# 3V3_MCU_SUPPLY.net
KiCad netlist of a schematic drawn in Altium Designer
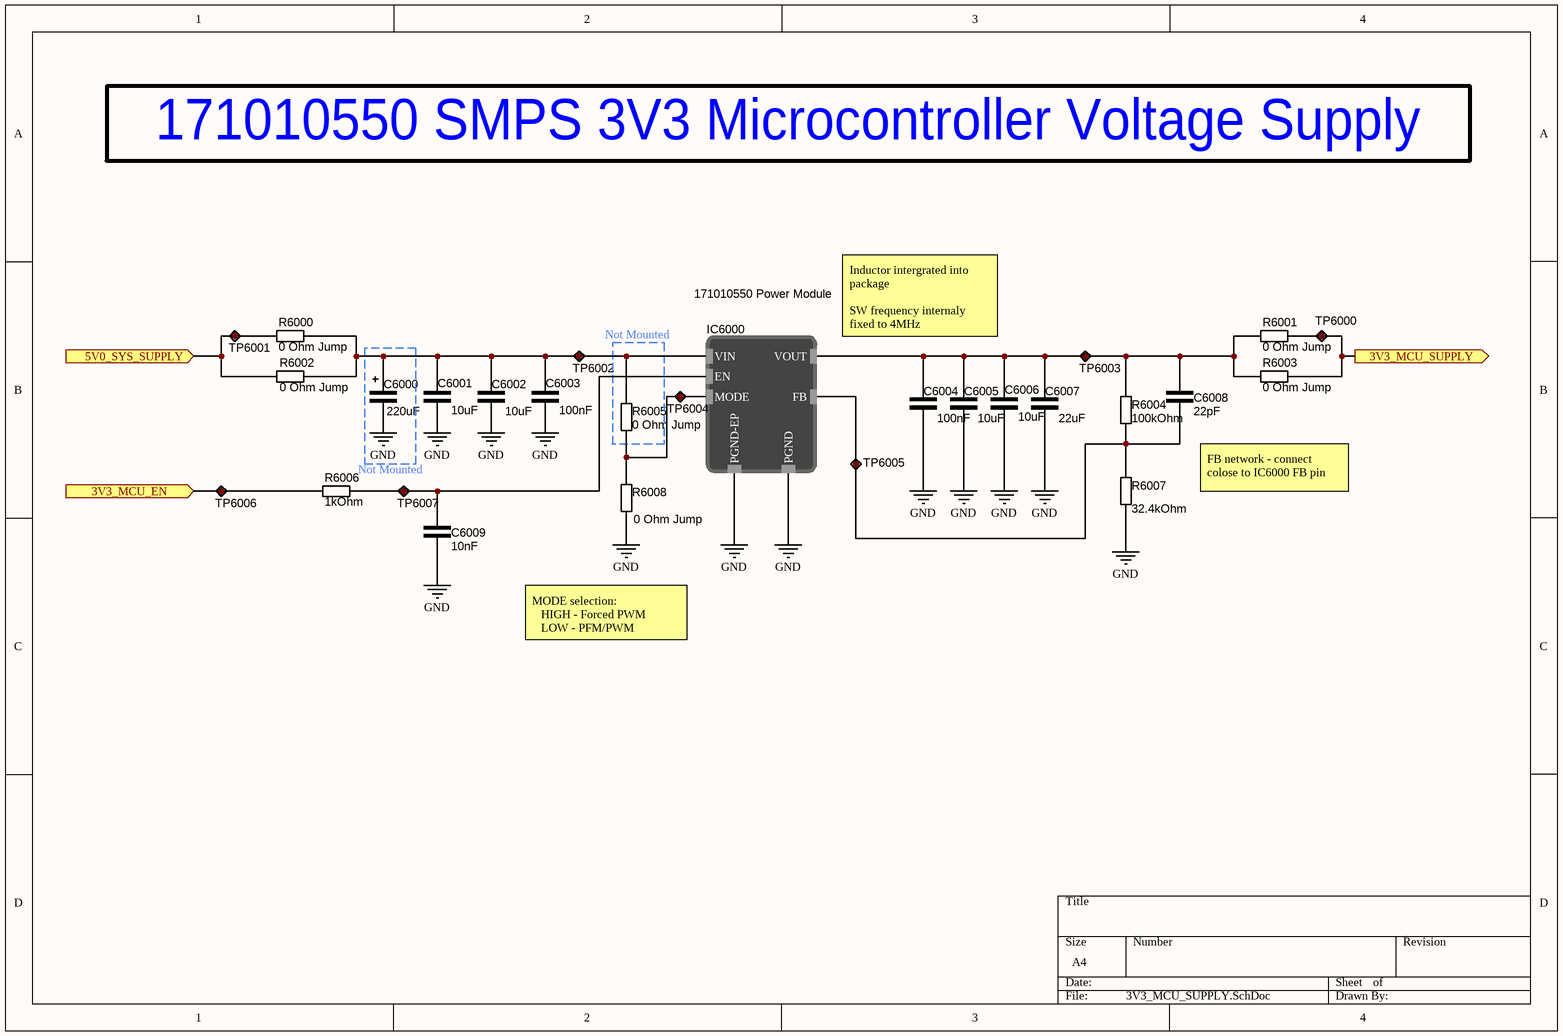
[diagram p0: 3V3_MCU_SUPPLY.SchDoc]

(export (version "E")
  (design (tool "Eeschema 10.0.6"))
  (components
    (comp (ref "C6000")
      (value "220uF")
      (footprint "CAPAE9083X100M")
      (description "220 µF 10 V Aluminum - Polymer Capacitors Radial, Can - SMD 20mOhm 2000 Hrs @ 105°C")
      (fields (field (name "DIGIKEY PART NUMBER") "399-A765KN227M1ALAE020CT-ND"))
      (libsource (lib "CapacitorsIntegrated") (part "C000025"))
    )
    (comp (ref "C6001")
      (value "10uF")
      (footprint "CAP_0805")
      (description "10 µF ±10% 25V Ceramic Capacitor X5R 0805 (2012 Metric)")
      (fields (field (name "DIGIKEY PART NUMBER") "445-5984-1-ND"))
      (libsource (lib "") (part "C000002_1"))
    )
    (comp (ref "C6002")
      (value "10uF")
      (footprint "CAP_0805")
      (description "10 µF ±10% 25V Ceramic Capacitor X5R 0805 (2012 Metric)")
      (fields (field (name "DIGIKEY PART NUMBER") "445-5984-1-ND"))
      (libsource (lib "CapacitorsIntegrated") (part "C000002"))
    )
    (comp (ref "C6003")
      (value "100nF")
      (footprint "CAP_0603")
      (description "0.1 µF ±10% 25V Ceramic Capacitor X7R 0603 (1608 Metric)")
      (fields (field (name "DIGIKEY PART NUMBER") "478-KAM15AR71E104KTCT-ND"))
      (libsource (lib "") (part "C000007_1"))
    )
    (comp (ref "C6004")
      (value "100nF")
      (footprint "CAP_0603")
      (description "0.1 µF ±10% 25V Ceramic Capacitor X7R 0603 (1608 Metric)")
      (fields (field (name "DIGIKEY PART NUMBER") "478-KAM15AR71E104KTCT-ND"))
      (libsource (lib "CapacitorsIntegrated") (part "C000007"))
    )
    (comp (ref "C6005")
      (value "10uF")
      (footprint "CAP_0805")
      (description "10 µF ±10% 25V Ceramic Capacitor X5R 0805 (2012 Metric)")
      (fields (field (name "DIGIKEY PART NUMBER") "445-5984-1-ND"))
      (libsource (lib "CapacitorsIntegrated") (part "C000002"))
    )
    (comp (ref "C6006")
      (value "10uF")
      (footprint "CAP_0805")
      (description "10 µF ±10% 25V Ceramic Capacitor X5R 0805 (2012 Metric)")
      (fields (field (name "DIGIKEY PART NUMBER") "445-5984-1-ND"))
      (libsource (lib "") (part "C000002_1"))
    )
    (comp (ref "C6007")
      (value "22uF")
      (footprint "CAP_0805")
      (description "22 µF ±20% 25V Ceramic Capacitor X5R 0805 (2012 Metric)")
      (fields (field (name "DIGIKEY PART NUMBER") "445-9112-1-ND"))
      (libsource (lib "CapacitorsIntegrated") (part "C000001"))
    )
    (comp (ref "C6008")
      (value "22pF")
      (footprint "CAP_0603")
      (description "22 pF ±10% 25V Ceramic Capacitor X7R 0603 (1608 Metric)")
      (fields (field (name "DIGIKEY PART NUMBER") "399-C0603C220K3RACAUTOCT-ND"))
      (libsource (lib "CapacitorsIntegrated") (part "C000024"))
    )
    (comp (ref "C6009")
      (value "10nF")
      (footprint "CAP_0603")
      (description "10000 pF ±20% 25V Ceramic Capacitor X7R 0603 (1608 Metric)")
      (fields (field (name "DIGIKEY PART NUMBER") "478-KGM15AR71E103MTCT-ND"))
      (libsource (lib "CapacitorsIntegrated") (part "C000005"))
    )
    (comp (ref "IC6000")
      (value "171010550 Power Module")
      (footprint "171010550")
      (description "Non-Isolated PoL Module DC DC Converter 1 Output 0.8 ~ 5.5V 1.2A 2.5V - 5.5V Input")
      (fields
        (field (name "DIGIKEY PART NUMBER") "732-171010550CT-ND")
        (field (name "MOUSER PART NUMBER") "710-171010550")
      )
      (libsource (lib "IntegratedCircuits") (part "171010550"))
    )
    (comp (ref "R6000")
      (value "0 Ohm Jump")
      (footprint "RES_0603")
      (description "0 Ohms Jumper Chip Resistor 0603 (1608 Metric) Automotive AEC-Q200 Thick Film")
      (fields (field (name "DIGIKEY PART NUMBER") "RMCF0603ZT0R00CT-ND"))
      (libsource (lib "") (part "R000007_1"))
    )
    (comp (ref "R6001")
      (value "0 Ohm Jump")
      (footprint "RES_0805")
      (description "0 Ohms Jumper Chip Resistor 0805 (2012 Metric) Automotive AEC-Q200 Thick Film")
      (fields (field (name "DIGIKEY PART NUMBER") "P0.0ACT-ND"))
      (libsource (lib "ResistorsIntegrated") (part "R000011"))
    )
    (comp (ref "R6002")
      (value "0 Ohm Jump")
      (footprint "RES_0603")
      (description "0 Ohms Jumper Chip Resistor 0603 (1608 Metric) Automotive AEC-Q200 Thick Film")
      (fields (field (name "DIGIKEY PART NUMBER") "RMCF0603ZT0R00CT-ND"))
      (libsource (lib "") (part "R000007_2"))
    )
    (comp (ref "R6003")
      (value "0 Ohm Jump")
      (footprint "RES_0805")
      (description "0 Ohms Jumper Chip Resistor 0805 (2012 Metric) Automotive AEC-Q200 Thick Film")
      (fields (field (name "DIGIKEY PART NUMBER") "P0.0ACT-ND"))
      (libsource (lib "ResistorsIntegrated") (part "R000011"))
    )
    (comp (ref "R6004")
      (value "100kOhm")
      (footprint "RES_0603")
      (description "100 kOhms ±1% 0.1W, 1/10W Chip Resistor 0603 (1608 Metric) Automotive AEC-Q200 Thick Film")
      (fields (field (name "DIGIKEY PART NUMBER") "RMCF0603FG100KCT-ND"))
      (libsource (lib "ResistorsIntegrated") (part "R000006"))
    )
    (comp (ref "R6005")
      (value "0 Ohm Jump")
      (footprint "RES_0603")
      (description "0 Ohms Jumper Chip Resistor 0603 (1608 Metric) Automotive AEC-Q200 Thick Film")
      (fields (field (name "DIGIKEY PART NUMBER") "RMCF0603ZT0R00CT-ND"))
      (libsource (lib "ResistorsIntegrated") (part "R000007"))
    )
    (comp (ref "R6006")
      (value "1kOhm")
      (footprint "RES_0603")
      (description "1 kOhms ±1% 0.125W, 1/8W Chip Resistor 0603 (1608 Metric) Anti-Sulfur Thin Film")
      (fields (field (name "DIGIKEY PART NUMBER") "MCT0603-1.00K-CFCT-ND"))
      (libsource (lib "ResistorsIntegrated") (part "R000004"))
    )
    (comp (ref "R6007")
      (value "32.4kOhm")
      (footprint "RES_0603")
      (description "32.4 kOhms ±1% 0.1W, 1/10W Chip Resistor 0603 (1608 Metric) Moisture Resistant Thick Film")
      (fields (field (name "DIGIKEY PART NUMBER") "CR0603-FX-3242ELFCT-ND"))
      (libsource (lib "ResistorsIntegrated") (part "R000014"))
    )
    (comp (ref "R6008")
      (value "0 Ohm Jump")
      (footprint "RES_0603")
      (description "0 Ohms Jumper Chip Resistor 0603 (1608 Metric) Automotive AEC-Q200 Thick Film")
      (fields (field (name "DIGIKEY PART NUMBER") "RMCF0603ZT0R00CT-ND"))
      (libsource (lib "ResistorsIntegrated") (part "R000007"))
    )
    (comp (ref "TP6000")
      (value "Test point")
      (footprint "TestPoint")
      (description "Test point 1mm")
      (libsource (lib "IntegratedCircuits") (part "TP002"))
    )
    (comp (ref "TP6001")
      (value "Test point")
      (footprint "TestPoint")
      (description "Test point 1mm")
      (libsource (lib "IntegratedCircuits") (part "TP002"))
    )
    (comp (ref "TP6002")
      (value "Test point")
      (footprint "TestPoint")
      (description "Test point 1mm")
      (libsource (lib "IntegratedCircuits") (part "TP002"))
    )
    (comp (ref "TP6003")
      (value "Test point")
      (footprint "TestPoint")
      (description "Test point 1mm")
      (libsource (lib "IntegratedCircuits") (part "TP002"))
    )
    (comp (ref "TP6004")
      (value "Test point")
      (footprint "TestPoint")
      (description "Test point 1mm")
      (libsource (lib "IntegratedCircuits") (part "TP002"))
    )
    (comp (ref "TP6005")
      (value "Test point")
      (footprint "TestPoint")
      (description "Test point 1mm")
      (libsource (lib "IntegratedCircuits") (part "TP002"))
    )
    (comp (ref "TP6006")
      (value "Test point")
      (footprint "TestPoint")
      (description "Test point 1mm")
      (libsource (lib "IntegratedCircuits") (part "TP002"))
    )
    (comp (ref "TP6007")
      (value "Test point")
      (footprint "TestPoint")
      (description "Test point 1mm")
      (libsource (lib "IntegratedCircuits") (part "TP002"))
    )
  )
  (nets
    (net (code "1") (name "/3V3_MCU_EN") (class "Default")
      (node (ref "R6006") (pin "1") (pinfunction "1_1") (pintype "passive"))
      (node (ref "TP6006") (pin "1") (pinfunction "1_1") (pintype "passive"))
    )
    (net (code "2") (name "/3V3_MCU_SUPPLY") (class "Default")
      (node (ref "R6001") (pin "2") (pinfunction "2_2") (pintype "passive"))
      (node (ref "R6003") (pin "2") (pinfunction "2_2") (pintype "passive"))
      (node (ref "TP6000") (pin "1") (pinfunction "1_1") (pintype "passive"))
    )
    (net (code "3") (name "/5V0_SYS_SUPPLY") (class "Default")
      (node (ref "R6000") (pin "1") (pinfunction "1_1") (pintype "passive"))
      (node (ref "R6002") (pin "2") (pinfunction "2_2") (pintype "passive"))
      (node (ref "TP6001") (pin "1") (pinfunction "1_1") (pintype "passive"))
    )
    (net (code "4") (name "GND") (class "Default")
      (node (ref "C6004") (pin "1") (pinfunction "1_1") (pintype "passive"))
      (node (ref "C6005") (pin "1") (pinfunction "1_1") (pintype "passive"))
      (node (ref "C6006") (pin "2") (pinfunction "2_2") (pintype "passive"))
      (node (ref "C6007") (pin "2") (pinfunction "2_2") (pintype "passive"))
      (node (ref "C6009") (pin "1") (pinfunction "1_1") (pintype "passive"))
      (node (ref "IC6000") (pin "5") (pinfunction "PGND_5") (pintype "passive"))
      (node (ref "IC6000") (pin "EP") (pinfunction "PGND-EP_EP") (pintype "passive"))
      (node (ref "R6007") (pin "1") (pinfunction "1_1") (pintype "passive"))
      (node (ref "R6008") (pin "1") (pinfunction "1_1") (pintype "passive"))
    )
    (net (code "5") (name "Net-(IC6000-EN)") (class "Default")
      (node (ref "C6009") (pin "2") (pinfunction "2_2") (pintype "passive"))
      (node (ref "IC6000") (pin "3") (pinfunction "EN_3") (pintype "passive"))
      (node (ref "R6006") (pin "2") (pinfunction "2_2") (pintype "passive"))
      (node (ref "TP6007") (pin "1") (pinfunction "1_1") (pintype "passive"))
    )
    (net (code "6") (name "Net-(IC6000-FB)") (class "Default")
      (node (ref "C6008") (pin "1") (pinfunction "1_1") (pintype "passive"))
      (node (ref "IC6000") (pin "1") (pinfunction "FB_1") (pintype "passive"))
      (node (ref "R6004") (pin "1") (pinfunction "1_1") (pintype "passive"))
      (node (ref "R6007") (pin "2") (pinfunction "2_2") (pintype "passive"))
      (node (ref "TP6005") (pin "1") (pinfunction "1_1") (pintype "passive"))
    )
    (net (code "7") (name "Net-(IC6000-MODE)") (class "Default")
      (node (ref "IC6000") (pin "2") (pinfunction "MODE_2") (pintype "passive"))
      (node (ref "R6005") (pin "1") (pinfunction "1_1") (pintype "passive"))
      (node (ref "R6008") (pin "2") (pinfunction "2_2") (pintype "passive"))
      (node (ref "TP6004") (pin "1") (pinfunction "1_1") (pintype "passive"))
    )
    (net (code "8") (name "Net-(IC6000-VIN)") (class "Default")
      (node (ref "C6000") (pin "2") (pinfunction "2_2") (pintype "passive"))
      (node (ref "C6001") (pin "1") (pinfunction "1_1") (pintype "passive"))
      (node (ref "C6002") (pin "2") (pinfunction "2_2") (pintype "passive"))
      (node (ref "C6003") (pin "1") (pinfunction "1_1") (pintype "passive"))
      (node (ref "IC6000") (pin "4") (pinfunction "VIN_4") (pintype "passive"))
      (node (ref "R6000") (pin "2") (pinfunction "2_2") (pintype "passive"))
      (node (ref "R6002") (pin "1") (pinfunction "1_1") (pintype "passive"))
      (node (ref "R6005") (pin "2") (pinfunction "2_2") (pintype "passive"))
      (node (ref "TP6002") (pin "1") (pinfunction "1_1") (pintype "passive"))
    )
    (net (code "9") (name "Net-(IC6000-VOUT)") (class "Default")
      (node (ref "C6004") (pin "2") (pinfunction "2_2") (pintype "passive"))
      (node (ref "C6005") (pin "2") (pinfunction "2_2") (pintype "passive"))
      (node (ref "C6006") (pin "1") (pinfunction "1_1") (pintype "passive"))
      (node (ref "C6007") (pin "1") (pinfunction "1_1") (pintype "passive"))
      (node (ref "C6008") (pin "2") (pinfunction "2_2") (pintype "passive"))
      (node (ref "IC6000") (pin "6") (pinfunction "VOUT_6") (pintype "passive"))
      (node (ref "R6001") (pin "1") (pinfunction "1_1") (pintype "passive"))
      (node (ref "R6003") (pin "1") (pinfunction "1_1") (pintype "passive"))
      (node (ref "R6004") (pin "2") (pinfunction "2_2") (pintype "passive"))
      (node (ref "TP6003") (pin "1") (pinfunction "1_1") (pintype "passive"))
    )
    (net (code "10") (name "unconnected-(C6000-Pad1)") (class "Default")
      (node (ref "C6000") (pin "1") (pinfunction "1_1") (pintype "passive"))
    )
    (net (code "11") (name "unconnected-(C6001-Pad2)") (class "Default")
      (node (ref "C6001") (pin "2") (pinfunction "2_2") (pintype "passive"))
    )
    (net (code "12") (name "unconnected-(C6002-Pad1)") (class "Default")
      (node (ref "C6002") (pin "1") (pinfunction "1_1") (pintype "passive"))
    )
    (net (code "13") (name "unconnected-(C6003-Pad2)") (class "Default")
      (node (ref "C6003") (pin "2") (pinfunction "2_2") (pintype "passive"))
    )
  )
)
